# MCU.net
KiCad netlist of a schematic drawn in Altium Designer
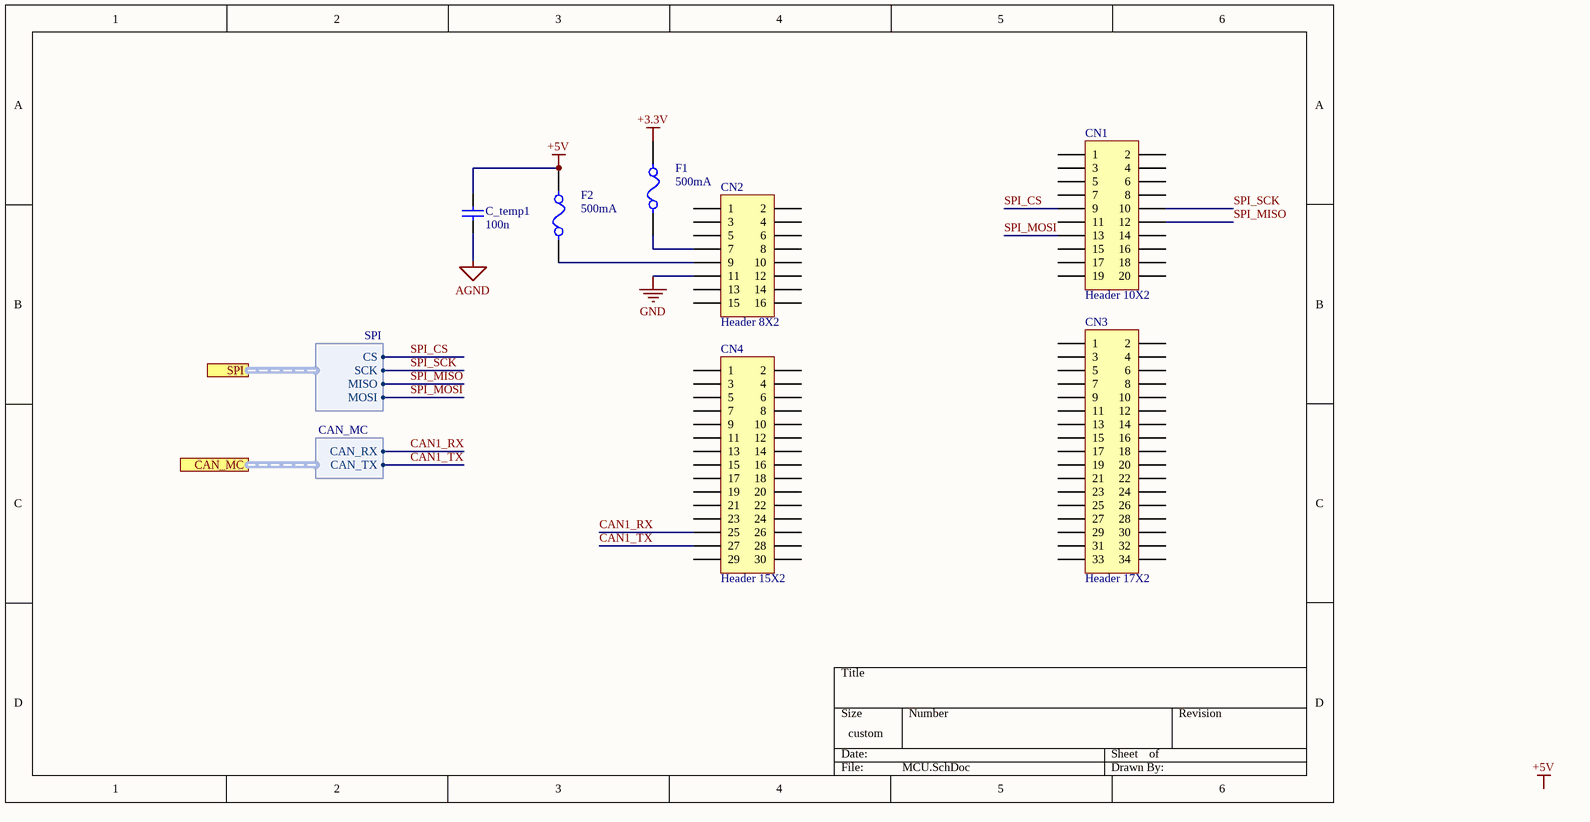
[diagram p0: MCU.SchDoc]

(export (version "E")
  (design (tool "Eeschema 10.0.6"))
  (components
    (comp (ref "CN1")
      (value "Header 10X2")
      (footprint "HDR2X10")
      (description "Header, 10-Pin, Dual row")
      (fields (field (name "PUBLISHER") "Altium Limited"))
      (libsource (lib "Miscellaneous Connectors") (part "Header 10X2"))
    )
    (comp (ref "CN2")
      (value "Header 8X2")
      (footprint "HDR2X8")
      (description "Header, 8-Pin, Dual row")
      (fields (field (name "PUBLISHER") "Altium Limited"))
      (libsource (lib "Miscellaneous Connectors") (part "Header 8X2"))
    )
    (comp (ref "CN3")
      (value "Header 17X2")
      (footprint "HDR2X17")
      (description "Header, 17-Pin, Dual row")
      (fields (field (name "PUBLISHER") "Altium Limited"))
      (libsource (lib "Miscellaneous Connectors") (part "Header 17X2"))
    )
    (comp (ref "CN4")
      (value "Header 15X2")
      (footprint "HDR2X15")
      (description "Header, 15-Pin, Dual row")
      (fields (field (name "PUBLISHER") "Altium Limited"))
      (libsource (lib "Miscellaneous Connectors") (part "Header 15X2"))
    )
    (comp (ref "C_temp1")
      (value "100n")
      (footprint "CAPC0603(1608)55_N")
      (description "Keramikvielschichtkondensator, SMD, Baureihe MC, ± 10%")
      (fields (field (name "MANUFACTURER") "TDK") (field (name "TOLERANCE") "± 10%"))
      (libsource (lib "Res&Caps") (part "Cap 100n"))
    )
    (comp (ref "F1")
      (value "500mA")
      (footprint "Fuse_500_mA")
      (description "0679H0500-01, Sicherungen zur Aufbaumontage 500mA 350 VAC 72 VCD")
      (libsource (lib "LV-BMS") (part "Fuse_500mA"))
    )
    (comp (ref "F2")
      (value "500mA")
      (footprint "Fuse_500_mA")
      (description "0679H0500-01, Sicherungen zur Aufbaumontage 500mA 350 VAC 72 VCD")
      (libsource (lib "LV-BMS") (part "Fuse_500mA"))
    )
  )
  (nets
    (net (code "3") (name "+3.3V") (class "Default")
      (node (ref "F1") (pin "2") (pinfunction "2_2") (pintype "passive"))
    )
    (net (code "4") (name "+5V") (class "Default")
      (node (ref "C_temp1") (pin "1") (pinfunction "1_1") (pintype "passive"))
      (node (ref "F2") (pin "2") (pinfunction "2_2") (pintype "passive"))
    )
    (net (code "5") (name "/CAN1_RX") (class "Default")
      (node (ref "CN4") (pin "25") (pinfunction "25_25") (pintype "passive"))
    )
    (net (code "6") (name "/CAN1_TX") (class "Default")
      (node (ref "CN4") (pin "27") (pinfunction "27_27") (pintype "passive"))
    )
    (net (code "7") (name "/SPI_CS") (class "Default")
      (node (ref "CN1") (pin "9") (pinfunction "9_9") (pintype "passive"))
    )
    (net (code "8") (name "/SPI_MISO") (class "Default")
      (node (ref "CN1") (pin "12") (pinfunction "12_12") (pintype "passive"))
    )
    (net (code "9") (name "/SPI_MOSI") (class "Default")
      (node (ref "CN1") (pin "13") (pinfunction "13_13") (pintype "passive"))
    )
    (net (code "10") (name "/SPI_SCK") (class "Default")
      (node (ref "CN1") (pin "10") (pinfunction "10_10") (pintype "passive"))
    )
    (net (code "13") (name "AGND") (class "Default")
      (node (ref "C_temp1") (pin "2") (pinfunction "2_2") (pintype "passive"))
    )
    (net (code "14") (name "GND") (class "Default")
      (node (ref "CN2") (pin "11") (pinfunction "11_11") (pintype "passive"))
    )
    (net (code "15") (name "Net-(CN2-Pad7)") (class "Default")
      (node (ref "CN2") (pin "7") (pinfunction "7_7") (pintype "passive"))
      (node (ref "F1") (pin "1") (pinfunction "1_1") (pintype "passive"))
    )
    (net (code "16") (name "Net-(CN2-Pad9)") (class "Default")
      (node (ref "CN2") (pin "9") (pinfunction "9_9") (pintype "passive"))
      (node (ref "F2") (pin "1") (pinfunction "1_1") (pintype "passive"))
    )
    (net (code "17") (name "unconnected-(CN1-Pad1)") (class "Default")
      (node (ref "CN1") (pin "1") (pinfunction "1_1") (pintype "passive"))
    )
    (net (code "18") (name "unconnected-(CN1-Pad2)") (class "Default")
      (node (ref "CN1") (pin "2") (pinfunction "2_2") (pintype "passive"))
    )
    (net (code "19") (name "unconnected-(CN1-Pad3)") (class "Default")
      (node (ref "CN1") (pin "3") (pinfunction "3_3") (pintype "passive"))
    )
    (net (code "20") (name "unconnected-(CN1-Pad4)") (class "Default")
      (node (ref "CN1") (pin "4") (pinfunction "4_4") (pintype "passive"))
    )
    (net (code "21") (name "unconnected-(CN1-Pad5)") (class "Default")
      (node (ref "CN1") (pin "5") (pinfunction "5_5") (pintype "passive"))
    )
    (net (code "22") (name "unconnected-(CN1-Pad6)") (class "Default")
      (node (ref "CN1") (pin "6") (pinfunction "6_6") (pintype "passive"))
    )
    (net (code "23") (name "unconnected-(CN1-Pad7)") (class "Default")
      (node (ref "CN1") (pin "7") (pinfunction "7_7") (pintype "passive"))
    )
    (net (code "24") (name "unconnected-(CN1-Pad8)") (class "Default")
      (node (ref "CN1") (pin "8") (pinfunction "8_8") (pintype "passive"))
    )
    (net (code "25") (name "unconnected-(CN1-Pad11)") (class "Default")
      (node (ref "CN1") (pin "11") (pinfunction "11_11") (pintype "passive"))
    )
    (net (code "26") (name "unconnected-(CN1-Pad14)") (class "Default")
      (node (ref "CN1") (pin "14") (pinfunction "14_14") (pintype "passive"))
    )
    (net (code "27") (name "unconnected-(CN1-Pad15)") (class "Default")
      (node (ref "CN1") (pin "15") (pinfunction "15_15") (pintype "passive"))
    )
    (net (code "28") (name "unconnected-(CN1-Pad16)") (class "Default")
      (node (ref "CN1") (pin "16") (pinfunction "16_16") (pintype "passive"))
    )
    (net (code "29") (name "unconnected-(CN1-Pad17)") (class "Default")
      (node (ref "CN1") (pin "17") (pinfunction "17_17") (pintype "passive"))
    )
    (net (code "30") (name "unconnected-(CN1-Pad18)") (class "Default")
      (node (ref "CN1") (pin "18") (pinfunction "18_18") (pintype "passive"))
    )
    (net (code "31") (name "unconnected-(CN1-Pad19)") (class "Default")
      (node (ref "CN1") (pin "19") (pinfunction "19_19") (pintype "passive"))
    )
    (net (code "32") (name "unconnected-(CN1-Pad20)") (class "Default")
      (node (ref "CN1") (pin "20") (pinfunction "20_20") (pintype "passive"))
    )
    (net (code "33") (name "unconnected-(CN2-Pad1)") (class "Default")
      (node (ref "CN2") (pin "1") (pinfunction "1_1") (pintype "passive"))
    )
    (net (code "34") (name "unconnected-(CN2-Pad2)") (class "Default")
      (node (ref "CN2") (pin "2") (pinfunction "2_2") (pintype "passive"))
    )
    (net (code "35") (name "unconnected-(CN2-Pad3)") (class "Default")
      (node (ref "CN2") (pin "3") (pinfunction "3_3") (pintype "passive"))
    )
    (net (code "36") (name "unconnected-(CN2-Pad4)") (class "Default")
      (node (ref "CN2") (pin "4") (pinfunction "4_4") (pintype "passive"))
    )
    (net (code "37") (name "unconnected-(CN2-Pad5)") (class "Default")
      (node (ref "CN2") (pin "5") (pinfunction "5_5") (pintype "passive"))
    )
    (net (code "38") (name "unconnected-(CN2-Pad6)") (class "Default")
      (node (ref "CN2") (pin "6") (pinfunction "6_6") (pintype "passive"))
    )
    (net (code "39") (name "unconnected-(CN2-Pad8)") (class "Default")
      (node (ref "CN2") (pin "8") (pinfunction "8_8") (pintype "passive"))
    )
    (net (code "40") (name "unconnected-(CN2-Pad10)") (class "Default")
      (node (ref "CN2") (pin "10") (pinfunction "10_10") (pintype "passive"))
    )
    (net (code "41") (name "unconnected-(CN2-Pad12)") (class "Default")
      (node (ref "CN2") (pin "12") (pinfunction "12_12") (pintype "passive"))
    )
    (net (code "42") (name "unconnected-(CN2-Pad13)") (class "Default")
      (node (ref "CN2") (pin "13") (pinfunction "13_13") (pintype "passive"))
    )
    (net (code "43") (name "unconnected-(CN2-Pad14)") (class "Default")
      (node (ref "CN2") (pin "14") (pinfunction "14_14") (pintype "passive"))
    )
    (net (code "44") (name "unconnected-(CN2-Pad15)") (class "Default")
      (node (ref "CN2") (pin "15") (pinfunction "15_15") (pintype "passive"))
    )
    (net (code "45") (name "unconnected-(CN2-Pad16)") (class "Default")
      (node (ref "CN2") (pin "16") (pinfunction "16_16") (pintype "passive"))
    )
    (net (code "46") (name "unconnected-(CN3-Pad1)") (class "Default")
      (node (ref "CN3") (pin "1") (pinfunction "1_1") (pintype "passive"))
    )
    (net (code "47") (name "unconnected-(CN3-Pad2)") (class "Default")
      (node (ref "CN3") (pin "2") (pinfunction "2_2") (pintype "passive"))
    )
    (net (code "48") (name "unconnected-(CN3-Pad3)") (class "Default")
      (node (ref "CN3") (pin "3") (pinfunction "3_3") (pintype "passive"))
    )
    (net (code "49") (name "unconnected-(CN3-Pad4)") (class "Default")
      (node (ref "CN3") (pin "4") (pinfunction "4_4") (pintype "passive"))
    )
    (net (code "50") (name "unconnected-(CN3-Pad5)") (class "Default")
      (node (ref "CN3") (pin "5") (pinfunction "5_5") (pintype "passive"))
    )
    (net (code "51") (name "unconnected-(CN3-Pad6)") (class "Default")
      (node (ref "CN3") (pin "6") (pinfunction "6_6") (pintype "passive"))
    )
    (net (code "52") (name "unconnected-(CN3-Pad7)") (class "Default")
      (node (ref "CN3") (pin "7") (pinfunction "7_7") (pintype "passive"))
    )
    (net (code "53") (name "unconnected-(CN3-Pad8)") (class "Default")
      (node (ref "CN3") (pin "8") (pinfunction "8_8") (pintype "passive"))
    )
    (net (code "54") (name "unconnected-(CN3-Pad9)") (class "Default")
      (node (ref "CN3") (pin "9") (pinfunction "9_9") (pintype "passive"))
    )
    (net (code "55") (name "unconnected-(CN3-Pad10)") (class "Default")
      (node (ref "CN3") (pin "10") (pinfunction "10_10") (pintype "passive"))
    )
    (net (code "56") (name "unconnected-(CN3-Pad11)") (class "Default")
      (node (ref "CN3") (pin "11") (pinfunction "11_11") (pintype "passive"))
    )
    (net (code "57") (name "unconnected-(CN3-Pad12)") (class "Default")
      (node (ref "CN3") (pin "12") (pinfunction "12_12") (pintype "passive"))
    )
    (net (code "58") (name "unconnected-(CN3-Pad13)") (class "Default")
      (node (ref "CN3") (pin "13") (pinfunction "13_13") (pintype "passive"))
    )
    (net (code "59") (name "unconnected-(CN3-Pad14)") (class "Default")
      (node (ref "CN3") (pin "14") (pinfunction "14_14") (pintype "passive"))
    )
    (net (code "60") (name "unconnected-(CN3-Pad15)") (class "Default")
      (node (ref "CN3") (pin "15") (pinfunction "15_15") (pintype "passive"))
    )
    (net (code "61") (name "unconnected-(CN3-Pad16)") (class "Default")
      (node (ref "CN3") (pin "16") (pinfunction "16_16") (pintype "passive"))
    )
    (net (code "62") (name "unconnected-(CN3-Pad17)") (class "Default")
      (node (ref "CN3") (pin "17") (pinfunction "17_17") (pintype "passive"))
    )
    (net (code "63") (name "unconnected-(CN3-Pad18)") (class "Default")
      (node (ref "CN3") (pin "18") (pinfunction "18_18") (pintype "passive"))
    )
    (net (code "64") (name "unconnected-(CN3-Pad19)") (class "Default")
      (node (ref "CN3") (pin "19") (pinfunction "19_19") (pintype "passive"))
    )
    (net (code "65") (name "unconnected-(CN3-Pad20)") (class "Default")
      (node (ref "CN3") (pin "20") (pinfunction "20_20") (pintype "passive"))
    )
    (net (code "66") (name "unconnected-(CN3-Pad21)") (class "Default")
      (node (ref "CN3") (pin "21") (pinfunction "21_21") (pintype "passive"))
    )
    (net (code "67") (name "unconnected-(CN3-Pad22)") (class "Default")
      (node (ref "CN3") (pin "22") (pinfunction "22_22") (pintype "passive"))
    )
    (net (code "68") (name "unconnected-(CN3-Pad23)") (class "Default")
      (node (ref "CN3") (pin "23") (pinfunction "23_23") (pintype "passive"))
    )
    (net (code "69") (name "unconnected-(CN3-Pad24)") (class "Default")
      (node (ref "CN3") (pin "24") (pinfunction "24_24") (pintype "passive"))
    )
    (net (code "70") (name "unconnected-(CN3-Pad25)") (class "Default")
      (node (ref "CN3") (pin "25") (pinfunction "25_25") (pintype "passive"))
    )
    (net (code "71") (name "unconnected-(CN3-Pad26)") (class "Default")
      (node (ref "CN3") (pin "26") (pinfunction "26_26") (pintype "passive"))
    )
    (net (code "72") (name "unconnected-(CN3-Pad27)") (class "Default")
      (node (ref "CN3") (pin "27") (pinfunction "27_27") (pintype "passive"))
    )
    (net (code "73") (name "unconnected-(CN3-Pad28)") (class "Default")
      (node (ref "CN3") (pin "28") (pinfunction "28_28") (pintype "passive"))
    )
    (net (code "74") (name "unconnected-(CN3-Pad29)") (class "Default")
      (node (ref "CN3") (pin "29") (pinfunction "29_29") (pintype "passive"))
    )
    (net (code "75") (name "unconnected-(CN3-Pad30)") (class "Default")
      (node (ref "CN3") (pin "30") (pinfunction "30_30") (pintype "passive"))
    )
    (net (code "76") (name "unconnected-(CN3-Pad31)") (class "Default")
      (node (ref "CN3") (pin "31") (pinfunction "31_31") (pintype "passive"))
    )
    (net (code "77") (name "unconnected-(CN3-Pad32)") (class "Default")
      (node (ref "CN3") (pin "32") (pinfunction "32_32") (pintype "passive"))
    )
    (net (code "78") (name "unconnected-(CN3-Pad33)") (class "Default")
      (node (ref "CN3") (pin "33") (pinfunction "33_33") (pintype "passive"))
    )
    (net (code "79") (name "unconnected-(CN3-Pad34)") (class "Default")
      (node (ref "CN3") (pin "34") (pinfunction "34_34") (pintype "passive"))
    )
    (net (code "80") (name "unconnected-(CN4-Pad1)") (class "Default")
      (node (ref "CN4") (pin "1") (pinfunction "1_1") (pintype "passive"))
    )
    (net (code "81") (name "unconnected-(CN4-Pad2)") (class "Default")
      (node (ref "CN4") (pin "2") (pinfunction "2_2") (pintype "passive"))
    )
    (net (code "82") (name "unconnected-(CN4-Pad3)") (class "Default")
      (node (ref "CN4") (pin "3") (pinfunction "3_3") (pintype "passive"))
    )
    (net (code "83") (name "unconnected-(CN4-Pad4)") (class "Default")
      (node (ref "CN4") (pin "4") (pinfunction "4_4") (pintype "passive"))
    )
    (net (code "84") (name "unconnected-(CN4-Pad5)") (class "Default")
      (node (ref "CN4") (pin "5") (pinfunction "5_5") (pintype "passive"))
    )
    (net (code "85") (name "unconnected-(CN4-Pad6)") (class "Default")
      (node (ref "CN4") (pin "6") (pinfunction "6_6") (pintype "passive"))
    )
    (net (code "86") (name "unconnected-(CN4-Pad7)") (class "Default")
      (node (ref "CN4") (pin "7") (pinfunction "7_7") (pintype "passive"))
    )
    (net (code "87") (name "unconnected-(CN4-Pad8)") (class "Default")
      (node (ref "CN4") (pin "8") (pinfunction "8_8") (pintype "passive"))
    )
    (net (code "88") (name "unconnected-(CN4-Pad9)") (class "Default")
      (node (ref "CN4") (pin "9") (pinfunction "9_9") (pintype "passive"))
    )
    (net (code "89") (name "unconnected-(CN4-Pad10)") (class "Default")
      (node (ref "CN4") (pin "10") (pinfunction "10_10") (pintype "passive"))
    )
    (net (code "90") (name "unconnected-(CN4-Pad11)") (class "Default")
      (node (ref "CN4") (pin "11") (pinfunction "11_11") (pintype "passive"))
    )
    (net (code "91") (name "unconnected-(CN4-Pad12)") (class "Default")
      (node (ref "CN4") (pin "12") (pinfunction "12_12") (pintype "passive"))
    )
    (net (code "92") (name "unconnected-(CN4-Pad13)") (class "Default")
      (node (ref "CN4") (pin "13") (pinfunction "13_13") (pintype "passive"))
    )
    (net (code "93") (name "unconnected-(CN4-Pad14)") (class "Default")
      (node (ref "CN4") (pin "14") (pinfunction "14_14") (pintype "passive"))
    )
    (net (code "94") (name "unconnected-(CN4-Pad15)") (class "Default")
      (node (ref "CN4") (pin "15") (pinfunction "15_15") (pintype "passive"))
    )
    (net (code "95") (name "unconnected-(CN4-Pad16)") (class "Default")
      (node (ref "CN4") (pin "16") (pinfunction "16_16") (pintype "passive"))
    )
    (net (code "96") (name "unconnected-(CN4-Pad17)") (class "Default")
      (node (ref "CN4") (pin "17") (pinfunction "17_17") (pintype "passive"))
    )
    (net (code "97") (name "unconnected-(CN4-Pad18)") (class "Default")
      (node (ref "CN4") (pin "18") (pinfunction "18_18") (pintype "passive"))
    )
    (net (code "98") (name "unconnected-(CN4-Pad19)") (class "Default")
      (node (ref "CN4") (pin "19") (pinfunction "19_19") (pintype "passive"))
    )
    (net (code "99") (name "unconnected-(CN4-Pad20)") (class "Default")
      (node (ref "CN4") (pin "20") (pinfunction "20_20") (pintype "passive"))
    )
    (net (code "100") (name "unconnected-(CN4-Pad21)") (class "Default")
      (node (ref "CN4") (pin "21") (pinfunction "21_21") (pintype "passive"))
    )
    (net (code "101") (name "unconnected-(CN4-Pad22)") (class "Default")
      (node (ref "CN4") (pin "22") (pinfunction "22_22") (pintype "passive"))
    )
    (net (code "102") (name "unconnected-(CN4-Pad23)") (class "Default")
      (node (ref "CN4") (pin "23") (pinfunction "23_23") (pintype "passive"))
    )
    (net (code "103") (name "unconnected-(CN4-Pad24)") (class "Default")
      (node (ref "CN4") (pin "24") (pinfunction "24_24") (pintype "passive"))
    )
    (net (code "104") (name "unconnected-(CN4-Pad26)") (class "Default")
      (node (ref "CN4") (pin "26") (pinfunction "26_26") (pintype "passive"))
    )
    (net (code "105") (name "unconnected-(CN4-Pad28)") (class "Default")
      (node (ref "CN4") (pin "28") (pinfunction "28_28") (pintype "passive"))
    )
    (net (code "106") (name "unconnected-(CN4-Pad29)") (class "Default")
      (node (ref "CN4") (pin "29") (pinfunction "29_29") (pintype "passive"))
    )
    (net (code "107") (name "unconnected-(CN4-Pad30)") (class "Default")
      (node (ref "CN4") (pin "30") (pinfunction "30_30") (pintype "passive"))
    )
  )
)
